# Page09_WIFI_Bluetooth.net
KiCad netlist of a schematic drawn in Altium Designer
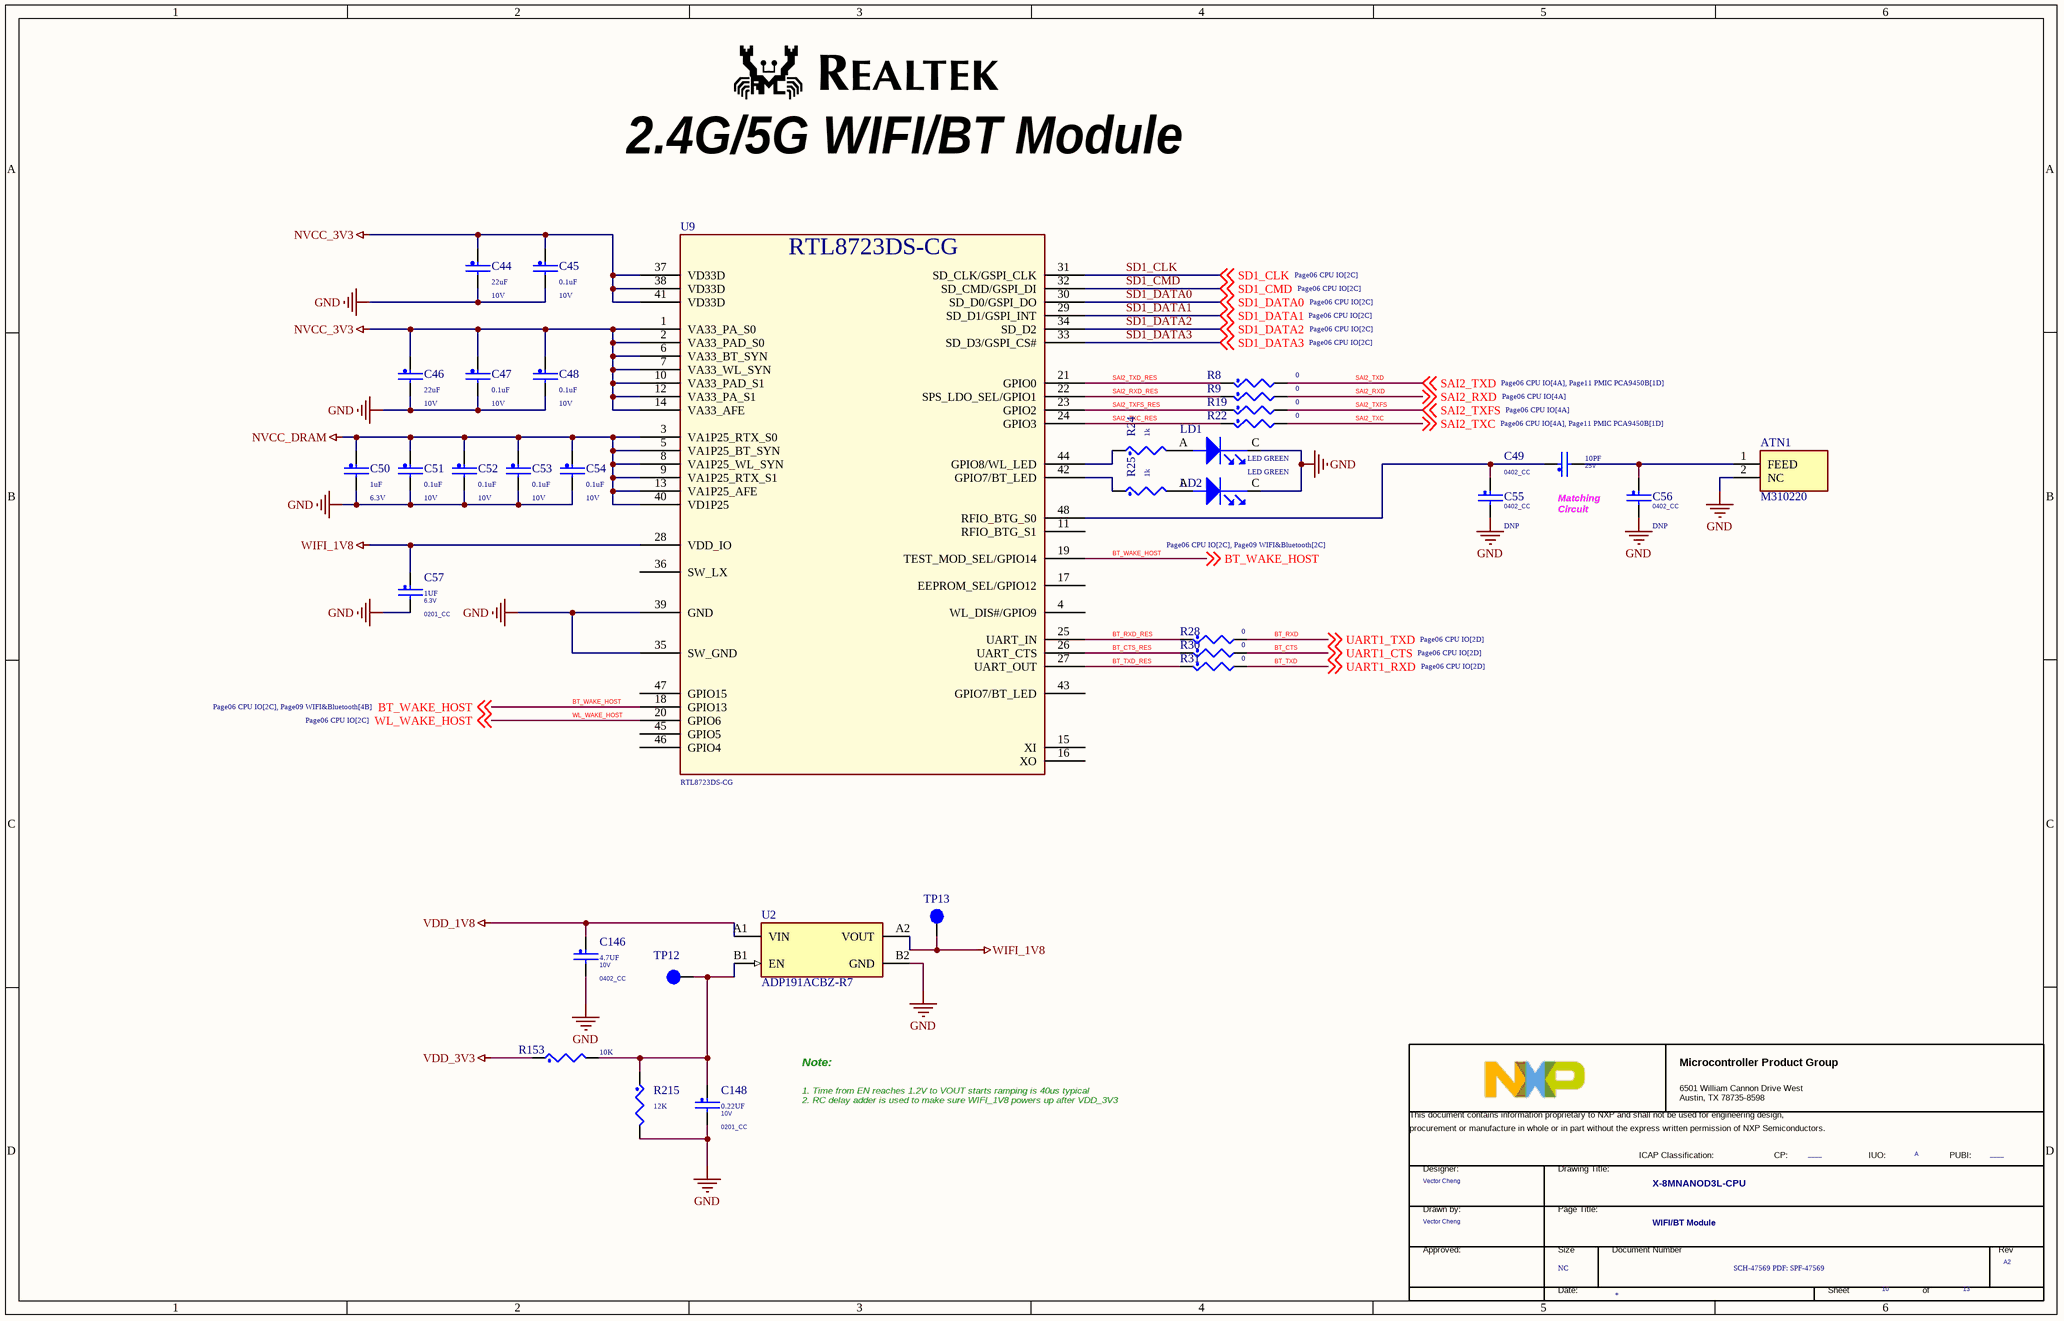
[diagram p0: Page09 WIFI&Bluetooth.SchDoc]

(export (version "E")
  (design (tool "Eeschema 10.0.6"))
  (components
    (comp (ref "*")
      (value "TitleBlock_MCPG")
      (fields
        (field (name "FCP") "____")
        (field (name "FIUO") "A")
        (field (name "PUBI") "____")
        (field (name "DRAWNBY") "Vector Cheng")
        (field (name "DESIGNER") "Vector Cheng")
        (field (name "PAGETITLE") "WIFI/BT Module")
        (field (name "PAGE COUNT") "13")
        (field (name "PAGE NUMBER") "10")
        (field (name "PAGE SIZE") "NC")
        (field (name "TITLE") "X-8MNANOD3L-CPU")
        (field (name "REVCODE") "A2")
        (field (name "DOC") "SCH-47569 PDF: SPF-47569")
      )
      (libsource (lib "*") (part "TitleBlock_MCPG"))
    )
    (comp (ref "ATN1")
      (value "M310220")
      (footprint "M310220")
      (description "Antennas Ceramic Chip ANTENNA BT/WLAN 2.4-2.5GHz")
      (libsource (lib "M310220") (part "M310220"))
    )
    (comp (ref "C44")
      (value "22uF")
      (footprint "0603_CC")
      (fields (field (name "VOLTAGE") "10V"))
      (libsource (lib "AA_iMX8_M_") (part "CAP_NP"))
    )
    (comp (ref "C45")
      (value "0.1uF")
      (footprint "0201_CC - C")
      (fields (field (name "VOLTAGE") "10V"))
      (libsource (lib "AA_iMX8_M_") (part "CAP_NP"))
    )
    (comp (ref "C46")
      (value "22uF")
      (footprint "0603_CC")
      (fields (field (name "VOLTAGE") "10V"))
      (libsource (lib "AA_iMX8_M_") (part "CAP_NP"))
    )
    (comp (ref "C47")
      (value "0.1uF")
      (footprint "0201_CC - C")
      (fields (field (name "VOLTAGE") "10V"))
      (libsource (lib "AA_iMX8_M_") (part "CAP_NP"))
    )
    (comp (ref "C48")
      (value "0.1uF")
      (footprint "0201_CC - C")
      (fields (field (name "VOLTAGE") "10V"))
      (libsource (lib "AA_iMX8_M_") (part "CAP_NP"))
    )
    (comp (ref "C49")
      (value "10PF")
      (footprint "0402_CC - C")
      (description "CAP CER 10PF 25V 5% C0G 0402")
      (fields
        (field (name "VOLTAGE") "25V")
        (field (name "TOLERANCE") "5%")
        (field (name "PCB FOOTPRINT") "0402_CC")
      )
      (libsource (lib "*") (part "CAP_NP"))
    )
    (comp (ref "C50")
      (value "1uF")
      (footprint "0201_CC - C")
      (fields (field (name "VOLTAGE") "6.3V"))
      (libsource (lib "AA_iMX8_M_") (part "CAP_NP"))
    )
    (comp (ref "C51")
      (value "0.1uF")
      (footprint "0201_CC - C")
      (fields (field (name "VOLTAGE") "10V"))
      (libsource (lib "AA_iMX8_M_") (part "CAP_NP"))
    )
    (comp (ref "C52")
      (value "0.1uF")
      (footprint "0201_CC - C")
      (fields (field (name "VOLTAGE") "10V"))
      (libsource (lib "AA_iMX8_M_") (part "CAP_NP"))
    )
    (comp (ref "C53")
      (value "0.1uF")
      (footprint "0201_CC - C")
      (fields (field (name "VOLTAGE") "10V"))
      (libsource (lib "AA_iMX8_M_") (part "CAP_NP"))
    )
    (comp (ref "C54")
      (value "0.1uF")
      (footprint "0201_CC - C")
      (fields (field (name "VOLTAGE") "10V"))
      (libsource (lib "AA_iMX8_M_") (part "CAP_NP"))
    )
    (comp (ref "C55")
      (value "10PF")
      (footprint "0402_CC - C")
      (description "CAP CER 10PF 25V 5% C0G 0402")
      (fields
        (field (name "ASSY_OPT") "DNP")
        (field (name "TOLERANCE") "5%")
        (field (name "VOLTAGE") "25V")
        (field (name "PCB FOOTPRINT") "0402_CC")
      )
      (libsource (lib "*") (part "CAP_NP"))
    )
    (comp (ref "C56")
      (value "10PF")
      (footprint "0402_CC - C")
      (description "CAP CER 10PF 25V 5% C0G 0402")
      (fields
        (field (name "ASSY_OPT") "DNP")
        (field (name "VOLTAGE") "25V")
        (field (name "TOLERANCE") "5%")
        (field (name "PCB FOOTPRINT") "0402_CC")
      )
      (libsource (lib "*") (part "CAP_NP"))
    )
    (comp (ref "C57")
      (value "1UF")
      (footprint "0201_CC - C")
      (description "CAP CER 1uF 6.3V 20% X5R 0201")
      (fields
        (field (name "PCB FOOTPRINT") "0201_CC")
        (field (name "TOLERANCE") "20%")
        (field (name "VOLTAGE") "6.3V")
      )
      (libsource (lib "*") (part "CAP_NP"))
    )
    (comp (ref "C146")
      (value "4.7UF")
      (footprint "0402_CC - C")
      (description "CAP CER 4.7uF 10V 10% X5R 0402")
      (fields
        (field (name "PCB FOOTPRINT") "0402_CC")
        (field (name "TOLERANCE") "10%")
        (field (name "VOLTAGE") "10V")
      )
      (libsource (lib "*") (part "CAP_NP"))
    )
    (comp (ref "C148")
      (value "0.22UF")
      (footprint "0201_CC - C")
      (description "CAP CER 0.22UF 10V 20% X5R 0201")
      (fields
        (field (name "VOLTAGE") "10V")
        (field (name "TOLERANCE") "20%")
        (field (name "PCB FOOTPRINT") "0201_CC")
      )
      (libsource (lib "*") (part "CAP_NP"))
    )
    (comp (ref "LD1")
      (value "LED GREEN")
      (footprint "LED_0603")
      (description "LED GRN SGL 25MA SMT 0603")
      (fields (field (name "VOLTAGE") "2V"))
      (libsource (lib "*") (part "LED"))
    )
    (comp (ref "LD2")
      (value "LED GREEN")
      (footprint "LED_0603")
      (description "LED GRN SGL 25MA SMT 0603")
      (fields (field (name "VOLTAGE") "2V"))
      (libsource (lib "*") (part "LED"))
    )
    (comp (ref "R8")
      (value "0")
      (footprint "0402_CC_RES")
      (description "RES MF ZERO OHM 1/16W 5% 0402")
      (fields (field (name "VOLTAGE") "1/16W") (field (name "TOLERANCE") "5%"))
      (libsource (lib "*") (part "RES"))
    )
    (comp (ref "R9")
      (value "0")
      (footprint "0402_CC_RES")
      (description "RES MF ZERO OHM 1/16W 5% 0402")
      (fields (field (name "VOLTAGE") "1/16W") (field (name "TOLERANCE") "5%"))
      (libsource (lib "*") (part "RES"))
    )
    (comp (ref "R19")
      (value "0")
      (footprint "0402_CC_RES")
      (description "RES MF ZERO OHM 1/16W 5% 0402")
      (fields (field (name "VOLTAGE") "1/16W") (field (name "TOLERANCE") "5%"))
      (libsource (lib "*") (part "RES"))
    )
    (comp (ref "R22")
      (value "0")
      (footprint "0402_CC_RES")
      (description "RES MF ZERO OHM 1/16W 5% 0402")
      (fields (field (name "VOLTAGE") "1/16W") (field (name "TOLERANCE") "5%"))
      (libsource (lib "*") (part "RES"))
    )
    (comp (ref "R24")
      (value "1k")
      (footprint "0201_RES")
      (description "RES MF 1.0K OHM 1/20W 1% 30V -55+155C 0201")
      (fields (field (name "VOLTAGE") "30") (field (name "TOLERANCE") "1%"))
      (libsource (lib "*") (part "RES"))
    )
    (comp (ref "R25")
      (value "1k")
      (footprint "0201_RES")
      (description "RES MF 1.0K OHM 1/20W 1% 30V -55+155C 0201")
      (fields (field (name "VOLTAGE") "30") (field (name "TOLERANCE") "1%"))
      (libsource (lib "*") (part "RES"))
    )
    (comp (ref "R28")
      (value "0")
      (footprint "0402_CC_RES")
      (description "RES MF ZERO OHM 1/16W 5% 0402")
      (fields (field (name "VOLTAGE") "1/16W") (field (name "TOLERANCE") "5%"))
      (libsource (lib "*") (part "RES"))
    )
    (comp (ref "R30")
      (value "0")
      (footprint "0402_CC_RES")
      (description "RES MF ZERO OHM 1/16W 5% 0402")
      (fields (field (name "VOLTAGE") "1/16W") (field (name "TOLERANCE") "5%"))
      (libsource (lib "*") (part "RES"))
    )
    (comp (ref "R31")
      (value "0")
      (footprint "0402_CC_RES")
      (description "RES MF ZERO OHM 1/16W 5% 0402")
      (fields (field (name "VOLTAGE") "1/16W") (field (name "TOLERANCE") "5%"))
      (libsource (lib "*") (part "RES"))
    )
    (comp (ref "R153")
      (value "10K")
      (footprint "0201_RES")
      (description "RES MF 10K 1/20W 5% 0201")
      (fields (field (name "TOLERANCE") "5%"))
      (libsource (lib "*") (part "RES"))
    )
    (comp (ref "R215")
      (value "12K")
      (footprint "0201_RES")
      (description "RES MF 12K 1/20W 1% 0201")
      (fields (field (name "VOLTAGE") "1/20W") (field (name "TOLERANCE") "1%"))
      (libsource (lib "*") (part "RES"))
    )
    (comp (ref "TP12")
      (value "tpad_020")
      (footprint "Test Pin")
      (description "TEST POINT PAD 0.5MM DIA SMT, NO PART TO ORDER")
      (libsource (lib "*") (part "TESTLOOP"))
    )
    (comp (ref "TP13")
      (value "tpad_020")
      (footprint "Test Pin")
      (description "TEST POINT PAD 0.5MM DIA SMT, NO PART TO ORDER")
      (libsource (lib "*") (part "TESTLOOP"))
    )
    (comp (ref "U2")
      (value "ADP191ACBZ-R7")
      (footprint "FP-CB-4-3-MFG")
      (description "IC PWR SWITCH P-CHAN 1:1 4WLCSP")
      (libsource (lib "Altium Content Vault") (part "55c8c918aceb6f1b08494a2ec7cb5d6"))
    )
    (comp (ref "U9")
      (value "RTL8723DS-CG")
      (footprint "RTL8723DS-CG")
      (libsource (lib "Altium starter project NANO") (part "RTL8723DS-CG"))
    )
  )
  (nets
    (net (code "1") (name "/BT_CTS_RES") (class "Default")
      (node (ref "R30") (pin "1") (pinfunction "1_1") (pintype "passive"))
      (node (ref "U9") (pin "26") (pinfunction "UART_CTS_26") (pintype "passive"))
    )
    (net (code "2") (name "/BT_RXD_RES") (class "Default")
      (node (ref "R28") (pin "1") (pinfunction "1_1") (pintype "passive"))
      (node (ref "U9") (pin "25") (pinfunction "UART_IN_25") (pintype "passive"))
    )
    (net (code "3") (name "/BT_TXD_RES") (class "Default")
      (node (ref "R31") (pin "1") (pinfunction "1_1") (pintype "passive"))
      (node (ref "U9") (pin "27") (pinfunction "UART_OUT_27") (pintype "passive"))
    )
    (net (code "4") (name "/SAI2_RXD_RES") (class "Default")
      (node (ref "R9") (pin "1") (pinfunction "1_1") (pintype "passive"))
      (node (ref "U9") (pin "22") (pinfunction "SPS_LDO_SEL/GPIO1_22") (pintype "passive"))
    )
    (net (code "5") (name "/SAI2_TXC_RES") (class "Default")
      (node (ref "R22") (pin "1") (pinfunction "1_1") (pintype "passive"))
      (node (ref "U9") (pin "24") (pinfunction "GPIO3_24") (pintype "passive"))
    )
    (net (code "6") (name "/SAI2_TXD_RES") (class "Default")
      (node (ref "R8") (pin "1") (pinfunction "1_1") (pintype "passive"))
      (node (ref "U9") (pin "21") (pinfunction "GPIO0_21") (pintype "passive"))
    )
    (net (code "7") (name "/SAI2_TXFS_RES") (class "Default")
      (node (ref "R19") (pin "1") (pinfunction "1_1") (pintype "passive"))
      (node (ref "U9") (pin "23") (pinfunction "GPIO2_23") (pintype "passive"))
    )
    (net (code "8") (name "BT_WAKE_HOST") (class "Default")
      (node (ref "U9") (pin "18") (pinfunction "GPIO13_18") (pintype "passive"))
      (node (ref "U9") (pin "19") (pinfunction "TEST_MOD_SEL/GPIO14_19") (pintype "passive"))
    )
    (net (code "9") (name "GND") (class "Default")
      (node (ref "ATN1") (pin "2") (pinfunction "NC_2") (pintype "passive"))
      (node (ref "C146") (pin "2") (pinfunction "2_2") (pintype "passive"))
      (node (ref "C148") (pin "2") (pinfunction "2_2") (pintype "passive"))
      (node (ref "C44") (pin "2") (pinfunction "2_2") (pintype "passive"))
      (node (ref "C45") (pin "2") (pinfunction "2_2") (pintype "passive"))
      (node (ref "C46") (pin "2") (pinfunction "2_2") (pintype "passive"))
      (node (ref "C47") (pin "2") (pinfunction "2_2") (pintype "passive"))
      (node (ref "C48") (pin "2") (pinfunction "2_2") (pintype "passive"))
      (node (ref "C50") (pin "2") (pinfunction "2_2") (pintype "passive"))
      (node (ref "C51") (pin "2") (pinfunction "2_2") (pintype "passive"))
      (node (ref "C52") (pin "2") (pinfunction "2_2") (pintype "passive"))
      (node (ref "C53") (pin "2") (pinfunction "2_2") (pintype "passive"))
      (node (ref "C54") (pin "2") (pinfunction "2_2") (pintype "passive"))
      (node (ref "C55") (pin "2") (pinfunction "2_2") (pintype "passive"))
      (node (ref "C56") (pin "2") (pinfunction "2_2") (pintype "passive"))
      (node (ref "C57") (pin "2") (pinfunction "2_2") (pintype "passive"))
      (node (ref "LD1") (pin "C") (pinfunction "CATHODE_C") (pintype "passive"))
      (node (ref "LD2") (pin "C") (pinfunction "CATHODE_C") (pintype "passive"))
      (node (ref "R215") (pin "2") (pinfunction "2_2") (pintype "passive"))
      (node (ref "U2") (pin "B2") (pinfunction "GND_B2") (pintype "power_in"))
      (node (ref "U9") (pin "35") (pinfunction "SW_GND_35") (pintype "passive"))
      (node (ref "U9") (pin "39") (pinfunction "GND_39") (pintype "passive"))
    )
    (net (code "10") (name "NVCC_3V3") (class "Default")
      (node (ref "C44") (pin "1") (pinfunction "1_1") (pintype "passive"))
      (node (ref "C45") (pin "1") (pinfunction "1_1") (pintype "passive"))
      (node (ref "C46") (pin "1") (pinfunction "1_1") (pintype "passive"))
      (node (ref "C47") (pin "1") (pinfunction "1_1") (pintype "passive"))
      (node (ref "C48") (pin "1") (pinfunction "1_1") (pintype "passive"))
      (node (ref "U9") (pin "1") (pinfunction "VA33_PA_S0_1") (pintype "passive"))
      (node (ref "U9") (pin "10") (pinfunction "VA33_PAD_S1_10") (pintype "passive"))
      (node (ref "U9") (pin "12") (pinfunction "VA33_PA_S1_12") (pintype "passive"))
      (node (ref "U9") (pin "14") (pinfunction "VA33_AFE_14") (pintype "passive"))
      (node (ref "U9") (pin "2") (pinfunction "VA33_PAD_S0_2") (pintype "passive"))
      (node (ref "U9") (pin "37") (pinfunction "VD33D_37") (pintype "passive"))
      (node (ref "U9") (pin "38") (pinfunction "VD33D_38") (pintype "passive"))
      (node (ref "U9") (pin "41") (pinfunction "VD33D_41") (pintype "passive"))
      (node (ref "U9") (pin "6") (pinfunction "VA33_BT_SYN_6") (pintype "passive"))
      (node (ref "U9") (pin "7") (pinfunction "VA33_WL_SYN_7") (pintype "passive"))
    )
    (net (code "11") (name "NVCC_DRAM") (class "Default")
      (node (ref "C50") (pin "1") (pinfunction "1_1") (pintype "passive"))
      (node (ref "C51") (pin "1") (pinfunction "1_1") (pintype "passive"))
      (node (ref "C52") (pin "1") (pinfunction "1_1") (pintype "passive"))
      (node (ref "C53") (pin "1") (pinfunction "1_1") (pintype "passive"))
      (node (ref "C54") (pin "1") (pinfunction "1_1") (pintype "passive"))
      (node (ref "U9") (pin "13") (pinfunction "VA1P25_AFE_13") (pintype "passive"))
      (node (ref "U9") (pin "3") (pinfunction "VA1P25_RTX_S0_3") (pintype "passive"))
      (node (ref "U9") (pin "40") (pinfunction "VD1P25_40") (pintype "passive"))
      (node (ref "U9") (pin "5") (pinfunction "VA1P25_BT_SYN_5") (pintype "passive"))
      (node (ref "U9") (pin "8") (pinfunction "VA1P25_WL_SYN_8") (pintype "passive"))
      (node (ref "U9") (pin "9") (pinfunction "VA1P25_RTX_S1_9") (pintype "passive"))
    )
    (net (code "12") (name "Net-(ATN1-FEED)") (class "Default")
      (node (ref "ATN1") (pin "1") (pinfunction "FEED_1") (pintype "passive"))
      (node (ref "C49") (pin "2") (pinfunction "2_2") (pintype "passive"))
      (node (ref "C56") (pin "1") (pinfunction "1_1") (pintype "passive"))
    )
    (net (code "13") (name "Net-(LD1-ANODE)") (class "Default")
      (node (ref "LD1") (pin "A") (pinfunction "ANODE_A") (pintype "passive"))
      (node (ref "R24") (pin "2") (pinfunction "2_2") (pintype "passive"))
    )
    (net (code "14") (name "Net-(LD2-ANODE)") (class "Default")
      (node (ref "LD2") (pin "A") (pinfunction "ANODE_A") (pintype "passive"))
      (node (ref "R25") (pin "2") (pinfunction "2_2") (pintype "passive"))
    )
    (net (code "15") (name "Net-(R25-Pad1)") (class "Default")
      (node (ref "R25") (pin "1") (pinfunction "1_1") (pintype "passive"))
      (node (ref "U9") (pin "42") (pinfunction "GPIO7/BT_LED_42") (pintype "passive"))
    )
    (net (code "16") (name "Net-(TP12-Pin1)") (class "Default")
      (node (ref "C148") (pin "1") (pinfunction "1_1") (pintype "passive"))
      (node (ref "R153") (pin "2") (pinfunction "2_2") (pintype "passive"))
      (node (ref "R215") (pin "1") (pinfunction "1_1") (pintype "passive"))
      (node (ref "TP12") (pin "1") (pinfunction "Pin1_1") (pintype "passive"))
      (node (ref "U2") (pin "B1") (pinfunction "EN_B1") (pintype "input"))
    )
    (net (code "17") (name "Net-(U9-GPIO8{slash}WL_LED)") (class "Default")
      (node (ref "R24") (pin "1") (pinfunction "1_1") (pintype "passive"))
      (node (ref "U9") (pin "44") (pinfunction "GPIO8/WL_LED_44") (pintype "passive"))
    )
    (net (code "18") (name "Net-(U9-RFIO_BTG_S0)") (class "Default")
      (node (ref "C49") (pin "1") (pinfunction "1_1") (pintype "passive"))
      (node (ref "C55") (pin "1") (pinfunction "1_1") (pintype "passive"))
      (node (ref "U9") (pin "48") (pinfunction "RFIO_BTG_S0_48") (pintype "passive"))
    )
    (net (code "19") (name "SAI2_RXD") (class "Default")
      (node (ref "R9") (pin "2") (pinfunction "2_2") (pintype "passive"))
    )
    (net (code "20") (name "SAI2_TXC") (class "Default")
      (node (ref "R22") (pin "2") (pinfunction "2_2") (pintype "passive"))
    )
    (net (code "21") (name "SAI2_TXD") (class "Default")
      (node (ref "R8") (pin "2") (pinfunction "2_2") (pintype "passive"))
    )
    (net (code "22") (name "SAI2_TXFS") (class "Default")
      (node (ref "R19") (pin "2") (pinfunction "2_2") (pintype "passive"))
    )
    (net (code "23") (name "SD1_CLK") (class "Default")
      (node (ref "U9") (pin "31") (pinfunction "SD_CLK/GSPI_CLK_31") (pintype "passive"))
    )
    (net (code "24") (name "SD1_CMD") (class "Default")
      (node (ref "U9") (pin "32") (pinfunction "SD_CMD/GSPI_DI_32") (pintype "passive"))
    )
    (net (code "25") (name "SD1_DATA0") (class "Default")
      (node (ref "U9") (pin "30") (pinfunction "SD_D0/GSPI_DO_30") (pintype "passive"))
    )
    (net (code "26") (name "SD1_DATA1") (class "Default")
      (node (ref "U9") (pin "29") (pinfunction "SD_D1/GSPI_INT_29") (pintype "passive"))
    )
    (net (code "27") (name "SD1_DATA2") (class "Default")
      (node (ref "U9") (pin "34") (pinfunction "SD_D2_34") (pintype "passive"))
    )
    (net (code "28") (name "SD1_DATA3") (class "Default")
      (node (ref "U9") (pin "33") (pinfunction "SD_D3/GSPI_CS#_33") (pintype "passive"))
    )
    (net (code "29") (name "UART1_CTS") (class "Default")
      (node (ref "R30") (pin "2") (pinfunction "2_2") (pintype "passive"))
    )
    (net (code "30") (name "UART1_RXD") (class "Default")
      (node (ref "R31") (pin "2") (pinfunction "2_2") (pintype "passive"))
    )
    (net (code "31") (name "UART1_TXD") (class "Default")
      (node (ref "R28") (pin "2") (pinfunction "2_2") (pintype "passive"))
    )
    (net (code "32") (name "VDD_1V8") (class "Default")
      (node (ref "C146") (pin "1") (pinfunction "1_1") (pintype "passive"))
      (node (ref "U2") (pin "A1") (pinfunction "VIN_A1") (pintype "power_in"))
    )
    (net (code "33") (name "VDD_3V3") (class "Default")
      (node (ref "R153") (pin "1") (pinfunction "1_1") (pintype "passive"))
    )
    (net (code "34") (name "WIFI_1V8") (class "Default")
      (node (ref "C57") (pin "1") (pinfunction "1_1") (pintype "passive"))
      (node (ref "TP13") (pin "1") (pinfunction "Pin1_1") (pintype "passive"))
      (node (ref "U2") (pin "A2") (pinfunction "VOUT_A2") (pintype "power_in"))
      (node (ref "U9") (pin "28") (pinfunction "VDD_IO_28") (pintype "passive"))
    )
    (net (code "35") (name "WL_WAKE_HOST") (class "Default")
      (node (ref "U9") (pin "20") (pinfunction "GPIO6_20") (pintype "passive"))
    )
    (net (code "36") (name "unconnected-(U9-EEPROM_SEL{slash}GPIO12-Pad17)") (class "Default")
      (node (ref "U9") (pin "17") (pinfunction "EEPROM_SEL/GPIO12_17") (pintype "passive"))
    )
    (net (code "37") (name "unconnected-(U9-GPIO4-Pad46)") (class "Default")
      (node (ref "U9") (pin "46") (pinfunction "GPIO4_46") (pintype "passive"))
    )
    (net (code "38") (name "unconnected-(U9-GPIO5-Pad45)") (class "Default")
      (node (ref "U9") (pin "45") (pinfunction "GPIO5_45") (pintype "passive"))
    )
    (net (code "39") (name "unconnected-(U9-GPIO7{slash}BT_LED-Pad43)") (class "Default")
      (node (ref "U9") (pin "43") (pinfunction "GPIO7/BT_LED_43") (pintype "passive"))
    )
    (net (code "40") (name "unconnected-(U9-GPIO15-Pad47)") (class "Default")
      (node (ref "U9") (pin "47") (pinfunction "GPIO15_47") (pintype "passive"))
    )
    (net (code "41") (name "unconnected-(U9-RFIO_BTG_S1-Pad11)") (class "Default")
      (node (ref "U9") (pin "11") (pinfunction "RFIO_BTG_S1_11") (pintype "passive"))
    )
    (net (code "42") (name "unconnected-(U9-SW_LX-Pad36)") (class "Default")
      (node (ref "U9") (pin "36") (pinfunction "SW_LX_36") (pintype "passive"))
    )
    (net (code "43") (name "unconnected-(U9-WL_DIS#{slash}GPIO9-Pad4)") (class "Default")
      (node (ref "U9") (pin "4") (pinfunction "WL_DIS#/GPIO9_4") (pintype "passive"))
    )
    (net (code "44") (name "unconnected-(U9-XI-Pad15)") (class "Default")
      (node (ref "U9") (pin "15") (pinfunction "XI_15") (pintype "passive"))
    )
    (net (code "45") (name "unconnected-(U9-XO-Pad16)") (class "Default")
      (node (ref "U9") (pin "16") (pinfunction "XO_16") (pintype "passive"))
    )
  )
)
